# lipo_charger.net
KiCad netlist of a schematic drawn in EAGLE
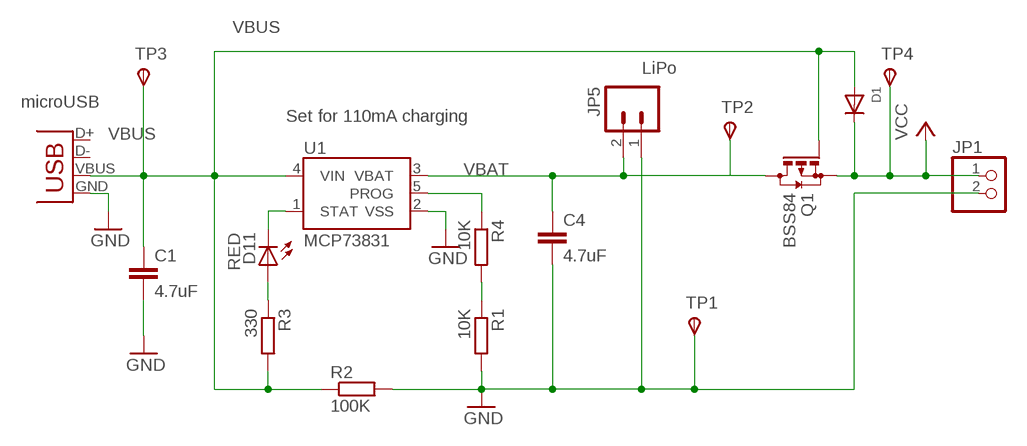
[diagram p0: schematic, sheet 1]

(export (version "E")
  (design (tool "Eeschema 10.0.6"))
  (components
    (comp (ref "C1")
      (value "4.7uF")
      (footprint "eagle-import:C0805")
      (libsource (lib "eagle-import") (part "C-EUC0805"))
    )
    (comp (ref "C4")
      (value "4.7uF")
      (footprint "eagle-import:C0805")
      (libsource (lib "eagle-import") (part "C-EUC0805"))
    )
    (comp (ref "D1")
      (value "DIODESOD-123")
      (footprint "eagle-import:SOD-123")
      (libsource (lib "eagle-import") (part "DIODESOD-123"))
    )
    (comp (ref "D11")
      (value "RED")
      (footprint "eagle-import:LED-1206")
      (libsource (lib "eagle-import") (part "LED1206"))
    )
    (comp (ref "JP1")
      (value "PINHD-1X2")
      (footprint "eagle-import:1X02")
      (libsource (lib "eagle-import") (part "PINHD-1X2"))
    )
    (comp (ref "JP5")
      (value "LiPo")
      (footprint "eagle-import:JST-2-PTH")
      (libsource (lib "eagle-import") (part "M02JST-PTH-2"))
    )
    (comp (ref "Q1")
      (value "BSS84")
      (footprint "eagle-import:SOT23")
      (libsource (lib "eagle-import") (part "BSS84"))
    )
    (comp (ref "R1")
      (value "10K")
      (footprint "eagle-import:R0805")
      (libsource (lib "eagle-import") (part "R-EU_R0805"))
    )
    (comp (ref "R2")
      (value "100K")
      (footprint "eagle-import:R0805")
      (libsource (lib "eagle-import") (part "R-EU_R0805"))
    )
    (comp (ref "R3")
      (value "330")
      (footprint "eagle-import:R0805")
      (libsource (lib "eagle-import") (part "R-EU_R0805"))
    )
    (comp (ref "R4")
      (value "10K")
      (footprint "eagle-import:R0805")
      (libsource (lib "eagle-import") (part "R-EU_R0805"))
    )
    (comp (ref "TP1")
      (value "TPSTP09R")
      (footprint "eagle-import:TP09R")
      (libsource (lib "eagle-import") (part "TPSTP09R"))
    )
    (comp (ref "TP2")
      (value "TPSTP09R")
      (footprint "eagle-import:TP09R")
      (libsource (lib "eagle-import") (part "TPSTP09R"))
    )
    (comp (ref "TP3")
      (value "TPSTP09R")
      (footprint "eagle-import:TP09R")
      (libsource (lib "eagle-import") (part "TPSTP09R"))
    )
    (comp (ref "TP4")
      (value "TPSTP09R")
      (footprint "eagle-import:TP09R")
      (libsource (lib "eagle-import") (part "TPSTP09R"))
    )
    (comp (ref "U1")
      (value "MCP73831")
      (footprint "eagle-import:SOT23-5")
      (libsource (lib "eagle-import") (part "MCP73831"))
    )
    (comp (ref "X1")
      (value "Mini USB B")
      (footprint "eagle-import:USB-MINIB-OLD")
      (libsource (lib "eagle-import") (part "USBOLD"))
    )
  )
  (nets
    (net (code "1") (name "/VBAT") (class "Default")
      (node (ref "C4") (pin "1") (pinfunction "1_1") (pintype "passive"))
      (node (ref "JP5") (pin "2") (pinfunction "2_2") (pintype "passive"))
      (node (ref "Q1") (pin "3") (pinfunction "D_3") (pintype "passive"))
      (node (ref "TP2") (pin "TP") (pinfunction "PP_TP") (pintype "input"))
      (node (ref "U1") (pin "3") (pinfunction "VBAT_3") (pintype "power_in"))
    )
    (net (code "2") (name "/VBUS") (class "Default")
      (node (ref "C1") (pin "1") (pinfunction "1_1") (pintype "passive"))
      (node (ref "D1") (pin "A") (pinfunction "A_A") (pintype "passive"))
      (node (ref "Q1") (pin "1") (pinfunction "G_1") (pintype "passive"))
      (node (ref "R2") (pin "1") (pinfunction "1_1") (pintype "passive"))
      (node (ref "R3") (pin "2") (pinfunction "2_2") (pintype "passive"))
      (node (ref "TP3") (pin "TP") (pinfunction "PP_TP") (pintype "input"))
      (node (ref "U1") (pin "4") (pinfunction "VIN_4") (pintype "power_in"))
      (node (ref "X1") (pin "VBUS") (pinfunction "VBUS_VBUS") (pintype "bidirectional"))
    )
    (net (code "3") (name "GND") (class "Default")
      (node (ref "C1") (pin "2") (pinfunction "2_2") (pintype "passive"))
      (node (ref "C4") (pin "2") (pinfunction "2_2") (pintype "passive"))
      (node (ref "JP1") (pin "2") (pinfunction "2_2") (pintype "passive"))
      (node (ref "JP5") (pin "1") (pinfunction "1_1") (pintype "passive"))
      (node (ref "R1") (pin "2") (pinfunction "2_2") (pintype "passive"))
      (node (ref "R2") (pin "2") (pinfunction "2_2") (pintype "passive"))
      (node (ref "TP1") (pin "TP") (pinfunction "PP_TP") (pintype "input"))
      (node (ref "U1") (pin "2") (pinfunction "VSS_2") (pintype "power_in"))
      (node (ref "X1") (pin "GND") (pinfunction "GND_GND") (pintype "bidirectional"))
    )
    (net (code "4") (name "Net-(D11-PadA)") (class "Default")
      (node (ref "D11") (pin "A") (pinfunction "A_A") (pintype "passive"))
      (node (ref "R3") (pin "1") (pinfunction "1_1") (pintype "passive"))
    )
    (net (code "5") (name "Net-(R1-Pad1)") (class "Default")
      (node (ref "R1") (pin "1") (pinfunction "1_1") (pintype "passive"))
      (node (ref "R4") (pin "2") (pinfunction "2_2") (pintype "passive"))
    )
    (net (code "6") (name "Net-(U1-PROG)") (class "Default")
      (node (ref "R4") (pin "1") (pinfunction "1_1") (pintype "passive"))
      (node (ref "U1") (pin "5") (pinfunction "PROG_5") (pintype "input"))
    )
    (net (code "7") (name "Net-(U1-STAT)") (class "Default")
      (node (ref "D11") (pin "C") (pinfunction "C_C") (pintype "passive"))
      (node (ref "U1") (pin "1") (pinfunction "STAT_1") (pintype "output"))
    )
    (net (code "8") (name "VCC") (class "Default")
      (node (ref "D1") (pin "C") (pinfunction "C_C") (pintype "passive"))
      (node (ref "JP1") (pin "1") (pinfunction "1_1") (pintype "passive"))
      (node (ref "Q1") (pin "2") (pinfunction "S_2") (pintype "passive"))
      (node (ref "TP4") (pin "TP") (pinfunction "PP_TP") (pintype "input"))
    )
    (net (code "9") (name "unconnected-(X1-PadD+)") (class "Default")
      (node (ref "X1") (pin "D+") (pinfunction "D+_D+") (pintype "bidirectional"))
    )
    (net (code "10") (name "unconnected-(X1-PadD-)") (class "Default")
      (node (ref "X1") (pin "D-") (pinfunction "D-_D-") (pintype "bidirectional"))
    )
  )
)
